# Log_and_Anti-Log_Converters_1.net
KiCad netlist of a schematic drawn in Altium Designer
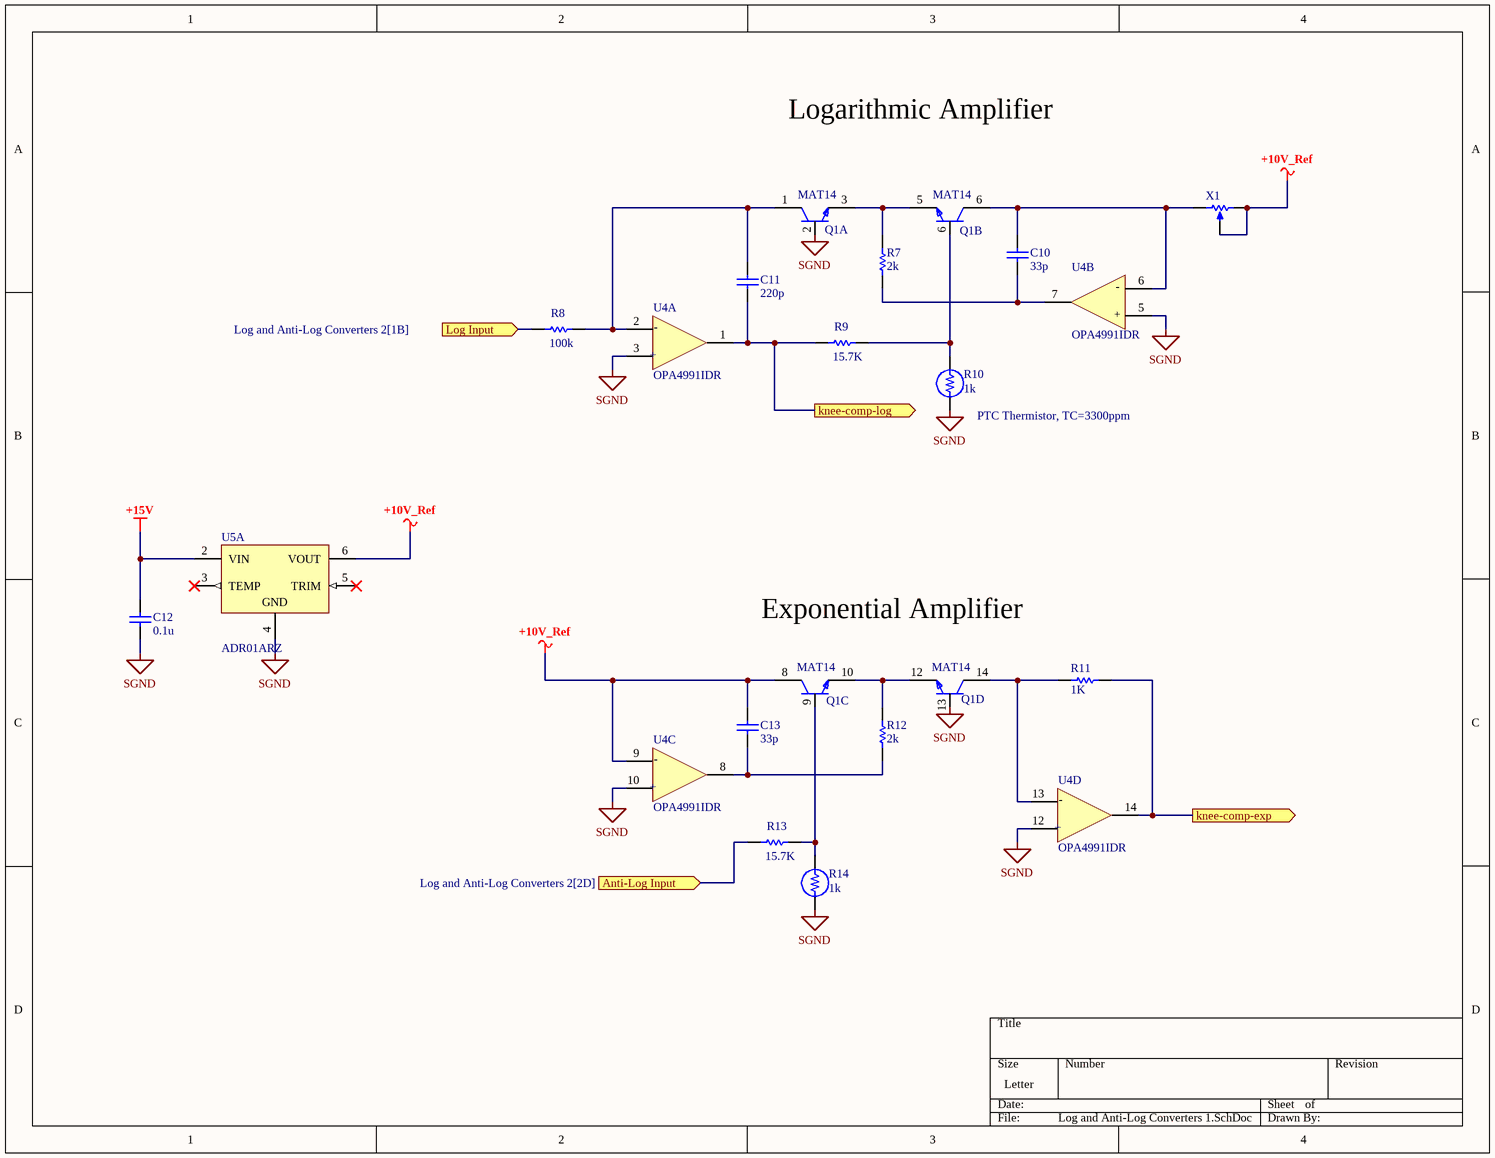
[diagram p0: Log and Anti-Log Converters 1.SchDoc]

(export (version "E")
  (design (tool "Eeschema 10.0.6"))
  (components
    (comp (ref "C10")
      (value "33p")
      (description "Capacitor")
      (libsource (lib "Simulation Generic Components") (part "Capacitor"))
    )
    (comp (ref "C11")
      (value "220p")
      (description "Capacitor")
      (libsource (lib "Simulation Generic Components") (part "Capacitor"))
    )
    (comp (ref "C12")
      (value "0.1u")
      (description "Capacitor")
      (libsource (lib "Simulation Generic Components") (part "Capacitor"))
    )
    (comp (ref "C13")
      (value "33p")
      (description "Capacitor")
      (libsource (lib "Simulation Generic Components") (part "Capacitor"))
    )
    (comp (ref "Q1")
      (value "MAT14")
      (footprint "FP-R-14-IPC_B")
      (description "TRANS 4NPN 40V 0.03A 14SO")
      (libsource (lib "DRC") (part "MAT14ARZ"))
    )
    (comp (ref "R7")
      (value "2k")
      (description "Resistor")
      (libsource (lib "Simulation Generic Components") (part "Resistor"))
    )
    (comp (ref "R8")
      (value "100k")
      (description "Resistor")
      (libsource (lib "Simulation Generic Components") (part "Resistor"))
    )
    (comp (ref "R9")
      (value "15.7K")
      (description "Resistor")
      (libsource (lib "Simulation Generic Components") (part "Resistor"))
    )
    (comp (ref "R10") (value "1k") (libsource (lib "DRC") (part "PTC Thermistor")))
    (comp (ref "R11")
      (value "1K")
      (description "Resistor")
      (libsource (lib "Simulation Generic Components") (part "Resistor"))
    )
    (comp (ref "R12")
      (value "2k")
      (description "Resistor")
      (libsource (lib "Simulation Generic Components") (part "Resistor"))
    )
    (comp (ref "R13")
      (value "15.7K")
      (description "Resistor")
      (libsource (lib "Simulation Generic Components") (part "Resistor"))
    )
    (comp (ref "R14") (value "1k") (libsource (lib "DRC") (part "PTC Thermistor")))
    (comp (ref "U4")
      (value "OPA4991IDR")
      (footprint "FP-D0014A-IPC_B")
      (description "40-V, DUAL 4.5MHZ, RAIL-TO-RAIL")
      (libsource (lib "") (part "OPA4991IDR_1"))
    )
    (comp (ref "U5")
      (value "ADR01ARZ")
      (footprint "ADI-R-8_M")
      (fields (field (name "MANUFACTURER") "Analog Devices"))
      (libsource (lib "Altium Content Vault") (part "ADI-REF0x_ADR0x-X-8"))
    )
    (comp (ref "X1")
      (value "Potentiometer")
      (libsource (lib "Simulation Generic Components") (part "Potentiometer"))
    )
  )
  (nets
    (net (code "1") (name "+10V_Ref") (class "Default")
      (node (ref "C13") (pin "2") (pinfunction "2_2") (pintype "passive"))
      (node (ref "Q1") (pin "8") (pinfunction "C3_8") (pintype "passive"))
      (node (ref "U4") (pin "9") (pinfunction "IN3-_9") (pintype "tri_state"))
      (node (ref "U5") (pin "6") (pinfunction "VOUT_6") (pintype "power_in"))
      (node (ref "X1") (pin "2") (pinfunction "BOT_2") (pintype "passive"))
      (node (ref "X1") (pin "3") (pinfunction "TAP_3") (pintype "passive"))
    )
    (net (code "2") (name "+15V") (class "Default")
      (node (ref "C12") (pin "2") (pinfunction "2_2") (pintype "passive"))
      (node (ref "U5") (pin "2") (pinfunction "VIN_2") (pintype "power_in"))
    )
    (net (code "3") (name "/Anti-Log Input") (class "Default")
      (node (ref "R13") (pin "2") (pinfunction "2_2") (pintype "passive"))
    )
    (net (code "4") (name "/Log Input") (class "Default")
      (node (ref "R8") (pin "2") (pinfunction "2_2") (pintype "passive"))
    )
    (net (code "5") (name "/knee-comp-exp") (class "Default")
      (node (ref "R11") (pin "2") (pinfunction "2_2") (pintype "passive"))
      (node (ref "U4") (pin "14") (pinfunction "OUT4_14") (pintype "passive"))
    )
    (net (code "6") (name "/knee-comp-log") (class "Default")
      (node (ref "C11") (pin "1") (pinfunction "1_1") (pintype "passive"))
      (node (ref "R9") (pin "2") (pinfunction "2_2") (pintype "passive"))
      (node (ref "U4") (pin "1") (pinfunction "OUT1_1") (pintype "passive"))
    )
    (net (code "7") (name "Net-(Q1A-C1)") (class "Default")
      (node (ref "C11") (pin "2") (pinfunction "2_2") (pintype "passive"))
      (node (ref "Q1") (pin "1") (pinfunction "C1_1") (pintype "passive"))
      (node (ref "R8") (pin "1") (pinfunction "1_1") (pintype "passive"))
      (node (ref "U4") (pin "2") (pinfunction "IN1-_2") (pintype "tri_state"))
    )
    (net (code "8") (name "Net-(Q1A-E1)") (class "Default")
      (node (ref "Q1") (pin "3") (pinfunction "E1_3") (pintype "passive"))
      (node (ref "Q1") (pin "5") (pinfunction "E2_5") (pintype "passive"))
      (node (ref "R7") (pin "2") (pinfunction "2_2") (pintype "passive"))
    )
    (net (code "9") (name "Net-(Q1B-B2)") (class "Default")
      (node (ref "Q1") (pin "6") (pinfunction "B2_6") (pintype "passive"))
      (node (ref "R10") (pin "2") (pinfunction "2_2") (pintype "passive"))
      (node (ref "R9") (pin "1") (pinfunction "1_1") (pintype "passive"))
    )
    (net (code "10") (name "Net-(Q1B-C2)") (class "Default")
      (node (ref "C10") (pin "2") (pinfunction "2_2") (pintype "passive"))
      (node (ref "Q1") (pin "6") (pinfunction "C2_6") (pintype "passive"))
      (node (ref "U4") (pin "6") (pinfunction "IN2-_6") (pintype "tri_state"))
      (node (ref "X1") (pin "1") (pinfunction "TOP_1") (pintype "passive"))
    )
    (net (code "11") (name "Net-(Q1C-B3)") (class "Default")
      (node (ref "Q1") (pin "9") (pinfunction "B3_9") (pintype "passive"))
      (node (ref "R13") (pin "1") (pinfunction "1_1") (pintype "passive"))
      (node (ref "R14") (pin "2") (pinfunction "2_2") (pintype "passive"))
    )
    (net (code "12") (name "Net-(Q1C-E3)") (class "Default")
      (node (ref "Q1") (pin "10") (pinfunction "E3_10") (pintype "passive"))
      (node (ref "Q1") (pin "12") (pinfunction "E4_12") (pintype "passive"))
      (node (ref "R12") (pin "2") (pinfunction "2_2") (pintype "passive"))
    )
    (net (code "13") (name "Net-(Q1D-C4)") (class "Default")
      (node (ref "Q1") (pin "14") (pinfunction "C4_14") (pintype "passive"))
      (node (ref "R11") (pin "1") (pinfunction "1_1") (pintype "passive"))
      (node (ref "U4") (pin "13") (pinfunction "IN4-_13") (pintype "tri_state"))
    )
    (net (code "14") (name "Net-(U4B-OUT2)") (class "Default")
      (node (ref "C10") (pin "1") (pinfunction "1_1") (pintype "passive"))
      (node (ref "R7") (pin "1") (pinfunction "1_1") (pintype "passive"))
      (node (ref "U4") (pin "7") (pinfunction "OUT2_7") (pintype "passive"))
    )
    (net (code "15") (name "Net-(U4C-OUT3)") (class "Default")
      (node (ref "C13") (pin "1") (pinfunction "1_1") (pintype "passive"))
      (node (ref "R12") (pin "1") (pinfunction "1_1") (pintype "passive"))
      (node (ref "U4") (pin "8") (pinfunction "OUT3_8") (pintype "passive"))
    )
    (net (code "16") (name "SGND") (class "Default")
      (node (ref "C12") (pin "1") (pinfunction "1_1") (pintype "passive"))
      (node (ref "Q1") (pin "13") (pinfunction "B4_13") (pintype "passive"))
      (node (ref "Q1") (pin "2") (pinfunction "B1_2") (pintype "passive"))
      (node (ref "R10") (pin "1") (pinfunction "1_1") (pintype "passive"))
      (node (ref "R14") (pin "1") (pinfunction "1_1") (pintype "passive"))
      (node (ref "U4") (pin "10") (pinfunction "IN3+_10") (pintype "tri_state"))
      (node (ref "U4") (pin "12") (pinfunction "IN4+_12") (pintype "tri_state"))
      (node (ref "U4") (pin "3") (pinfunction "IN1+_3") (pintype "tri_state"))
      (node (ref "U4") (pin "5") (pinfunction "IN2+_5") (pintype "tri_state"))
      (node (ref "U5") (pin "4") (pinfunction "GND_4") (pintype "power_in"))
    )
    (net (code "17") (name "unconnected-(U5A-TEMP-Pad3)") (class "Default")
      (node (ref "U5") (pin "3") (pinfunction "TEMP_3") (pintype "output+no_connect"))
    )
    (net (code "18") (name "unconnected-(U5A-TRIM-Pad5)") (class "Default")
      (node (ref "U5") (pin "5") (pinfunction "TRIM_5") (pintype "input+no_connect"))
    )
  )
)
